# pcb1.net
KiCad netlist of a schematic drawn in EAGLE
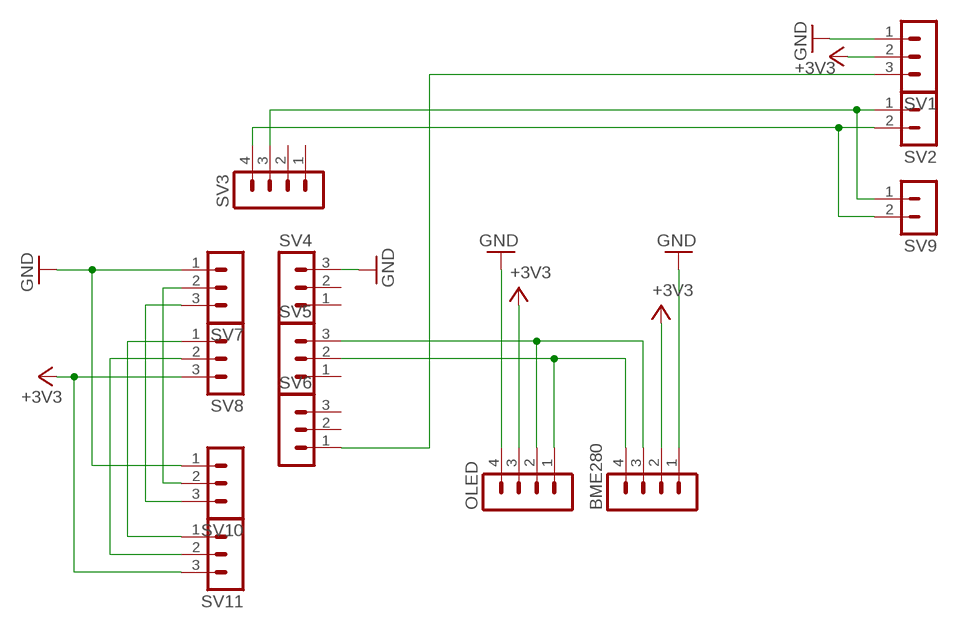
[diagram p0: schematic, sheet 1]

(export (version "E")
  (design (tool "Eeschema 10.0.6"))
  (components
    (comp (ref "BME280")
      (value "PINHEAD-MA04-1")
      (footprint "eagle-import:PINHEAD-MA04-1")
      (libsource (lib "eagle-import") (part "PINHEAD-MA04-1"))
    )
    (comp (ref "OLED")
      (value "PINHEAD-MA04-1")
      (footprint "eagle-import:PINHEAD-MA04-1")
      (libsource (lib "eagle-import") (part "PINHEAD-MA04-1"))
    )
    (comp (ref "SV1")
      (value "PINHEAD-MA03-1")
      (footprint "eagle-import:PINHEAD-MA03-1")
      (libsource (lib "eagle-import") (part "PINHEAD-MA03-1"))
    )
    (comp (ref "SV2")
      (value "PINHEAD-MA02-1")
      (footprint "eagle-import:PINHEAD-MA02-1")
      (libsource (lib "eagle-import") (part "PINHEAD-MA02-1"))
    )
    (comp (ref "SV3")
      (value "PINHEAD-MA04-1")
      (footprint "eagle-import:PINHEAD-MA04-1")
      (libsource (lib "eagle-import") (part "PINHEAD-MA04-1"))
    )
    (comp (ref "SV4")
      (value "PINHEAD-MA03-1")
      (footprint "eagle-import:PINHEAD-MA03-1")
      (libsource (lib "eagle-import") (part "PINHEAD-MA03-1"))
    )
    (comp (ref "SV5")
      (value "PINHEAD-MA03-1")
      (footprint "eagle-import:PINHEAD-MA03-1")
      (libsource (lib "eagle-import") (part "PINHEAD-MA03-1"))
    )
    (comp (ref "SV6")
      (value "PINHEAD-MA03-1")
      (footprint "eagle-import:PINHEAD-MA03-1")
      (libsource (lib "eagle-import") (part "PINHEAD-MA03-1"))
    )
    (comp (ref "SV7")
      (value "PINHEAD-MA03-1")
      (footprint "eagle-import:PINHEAD-MA03-1")
      (libsource (lib "eagle-import") (part "PINHEAD-MA03-1"))
    )
    (comp (ref "SV8")
      (value "PINHEAD-MA03-1")
      (footprint "eagle-import:PINHEAD-MA03-1")
      (libsource (lib "eagle-import") (part "PINHEAD-MA03-1"))
    )
    (comp (ref "SV9")
      (value "PINHEAD-MA02-1")
      (footprint "eagle-import:PINHEAD-MA02-1")
      (libsource (lib "eagle-import") (part "PINHEAD-MA02-1"))
    )
    (comp (ref "SV10")
      (value "PINHEAD-MA03-1")
      (footprint "eagle-import:PINHEAD-MA03-1")
      (libsource (lib "eagle-import") (part "PINHEAD-MA03-1"))
    )
    (comp (ref "SV11")
      (value "PINHEAD-MA03-1")
      (footprint "eagle-import:PINHEAD-MA03-1")
      (libsource (lib "eagle-import") (part "PINHEAD-MA03-1"))
    )
  )
  (nets
    (net (code "1") (name "+3V3") (class "Default")
      (node (ref "BME280") (pin "2") (pinfunction "2_2") (pintype "passive"))
      (node (ref "OLED") (pin "3") (pinfunction "3_3") (pintype "passive"))
      (node (ref "SV1") (pin "2") (pinfunction "2_2") (pintype "passive"))
      (node (ref "SV11") (pin "3") (pinfunction "3_3") (pintype "passive"))
      (node (ref "SV8") (pin "3") (pinfunction "3_3") (pintype "passive"))
    )
    (net (code "2") (name "GND") (class "Default")
      (node (ref "BME280") (pin "1") (pinfunction "1_1") (pintype "passive"))
      (node (ref "OLED") (pin "4") (pinfunction "4_4") (pintype "passive"))
      (node (ref "SV1") (pin "1") (pinfunction "1_1") (pintype "passive"))
      (node (ref "SV10") (pin "1") (pinfunction "1_1") (pintype "passive"))
      (node (ref "SV4") (pin "3") (pinfunction "3_3") (pintype "passive"))
      (node (ref "SV7") (pin "1") (pinfunction "1_1") (pintype "passive"))
    )
    (net (code "3") (name "Net-(BME280-Pad3)") (class "Default")
      (node (ref "BME280") (pin "3") (pinfunction "3_3") (pintype "passive"))
      (node (ref "OLED") (pin "2") (pinfunction "2_2") (pintype "passive"))
      (node (ref "SV5") (pin "3") (pinfunction "3_3") (pintype "passive"))
    )
    (net (code "4") (name "Net-(BME280-Pad4)") (class "Default")
      (node (ref "BME280") (pin "4") (pinfunction "4_4") (pintype "passive"))
      (node (ref "OLED") (pin "1") (pinfunction "1_1") (pintype "passive"))
      (node (ref "SV5") (pin "2") (pinfunction "2_2") (pintype "passive"))
    )
    (net (code "5") (name "Net-(SV1-Pad3)") (class "Default")
      (node (ref "SV1") (pin "3") (pinfunction "3_3") (pintype "passive"))
      (node (ref "SV6") (pin "1") (pinfunction "1_1") (pintype "passive"))
    )
    (net (code "6") (name "Net-(SV2-Pad1)") (class "Default")
      (node (ref "SV2") (pin "1") (pinfunction "1_1") (pintype "passive"))
      (node (ref "SV3") (pin "3") (pinfunction "3_3") (pintype "passive"))
      (node (ref "SV9") (pin "1") (pinfunction "1_1") (pintype "passive"))
    )
    (net (code "7") (name "Net-(SV2-Pad2)") (class "Default")
      (node (ref "SV2") (pin "2") (pinfunction "2_2") (pintype "passive"))
      (node (ref "SV3") (pin "4") (pinfunction "4_4") (pintype "passive"))
      (node (ref "SV9") (pin "2") (pinfunction "2_2") (pintype "passive"))
    )
    (net (code "8") (name "Net-(SV10-Pad2)") (class "Default")
      (node (ref "SV10") (pin "2") (pinfunction "2_2") (pintype "passive"))
      (node (ref "SV7") (pin "2") (pinfunction "2_2") (pintype "passive"))
    )
    (net (code "9") (name "Net-(SV10-Pad3)") (class "Default")
      (node (ref "SV10") (pin "3") (pinfunction "3_3") (pintype "passive"))
      (node (ref "SV7") (pin "3") (pinfunction "3_3") (pintype "passive"))
    )
    (net (code "10") (name "Net-(SV11-Pad1)") (class "Default")
      (node (ref "SV11") (pin "1") (pinfunction "1_1") (pintype "passive"))
      (node (ref "SV8") (pin "1") (pinfunction "1_1") (pintype "passive"))
    )
    (net (code "11") (name "Net-(SV11-Pad2)") (class "Default")
      (node (ref "SV11") (pin "2") (pinfunction "2_2") (pintype "passive"))
      (node (ref "SV8") (pin "2") (pinfunction "2_2") (pintype "passive"))
    )
    (net (code "12") (name "unconnected-(SV3-Pad1)") (class "Default")
      (node (ref "SV3") (pin "1") (pinfunction "1_1") (pintype "passive"))
    )
    (net (code "13") (name "unconnected-(SV3-Pad2)") (class "Default")
      (node (ref "SV3") (pin "2") (pinfunction "2_2") (pintype "passive"))
    )
    (net (code "14") (name "unconnected-(SV4-Pad1)") (class "Default")
      (node (ref "SV4") (pin "1") (pinfunction "1_1") (pintype "passive"))
    )
    (net (code "15") (name "unconnected-(SV4-Pad2)") (class "Default")
      (node (ref "SV4") (pin "2") (pinfunction "2_2") (pintype "passive"))
    )
    (net (code "16") (name "unconnected-(SV5-Pad1)") (class "Default")
      (node (ref "SV5") (pin "1") (pinfunction "1_1") (pintype "passive"))
    )
    (net (code "17") (name "unconnected-(SV6-Pad2)") (class "Default")
      (node (ref "SV6") (pin "2") (pinfunction "2_2") (pintype "passive"))
    )
    (net (code "18") (name "unconnected-(SV6-Pad3)") (class "Default")
      (node (ref "SV6") (pin "3") (pinfunction "3_3") (pintype "passive"))
    )
  )
)
